# ProDoc_Schematic1_2026-05-29.net
KiCad netlist of a schematic drawn in EasyEDA Pro
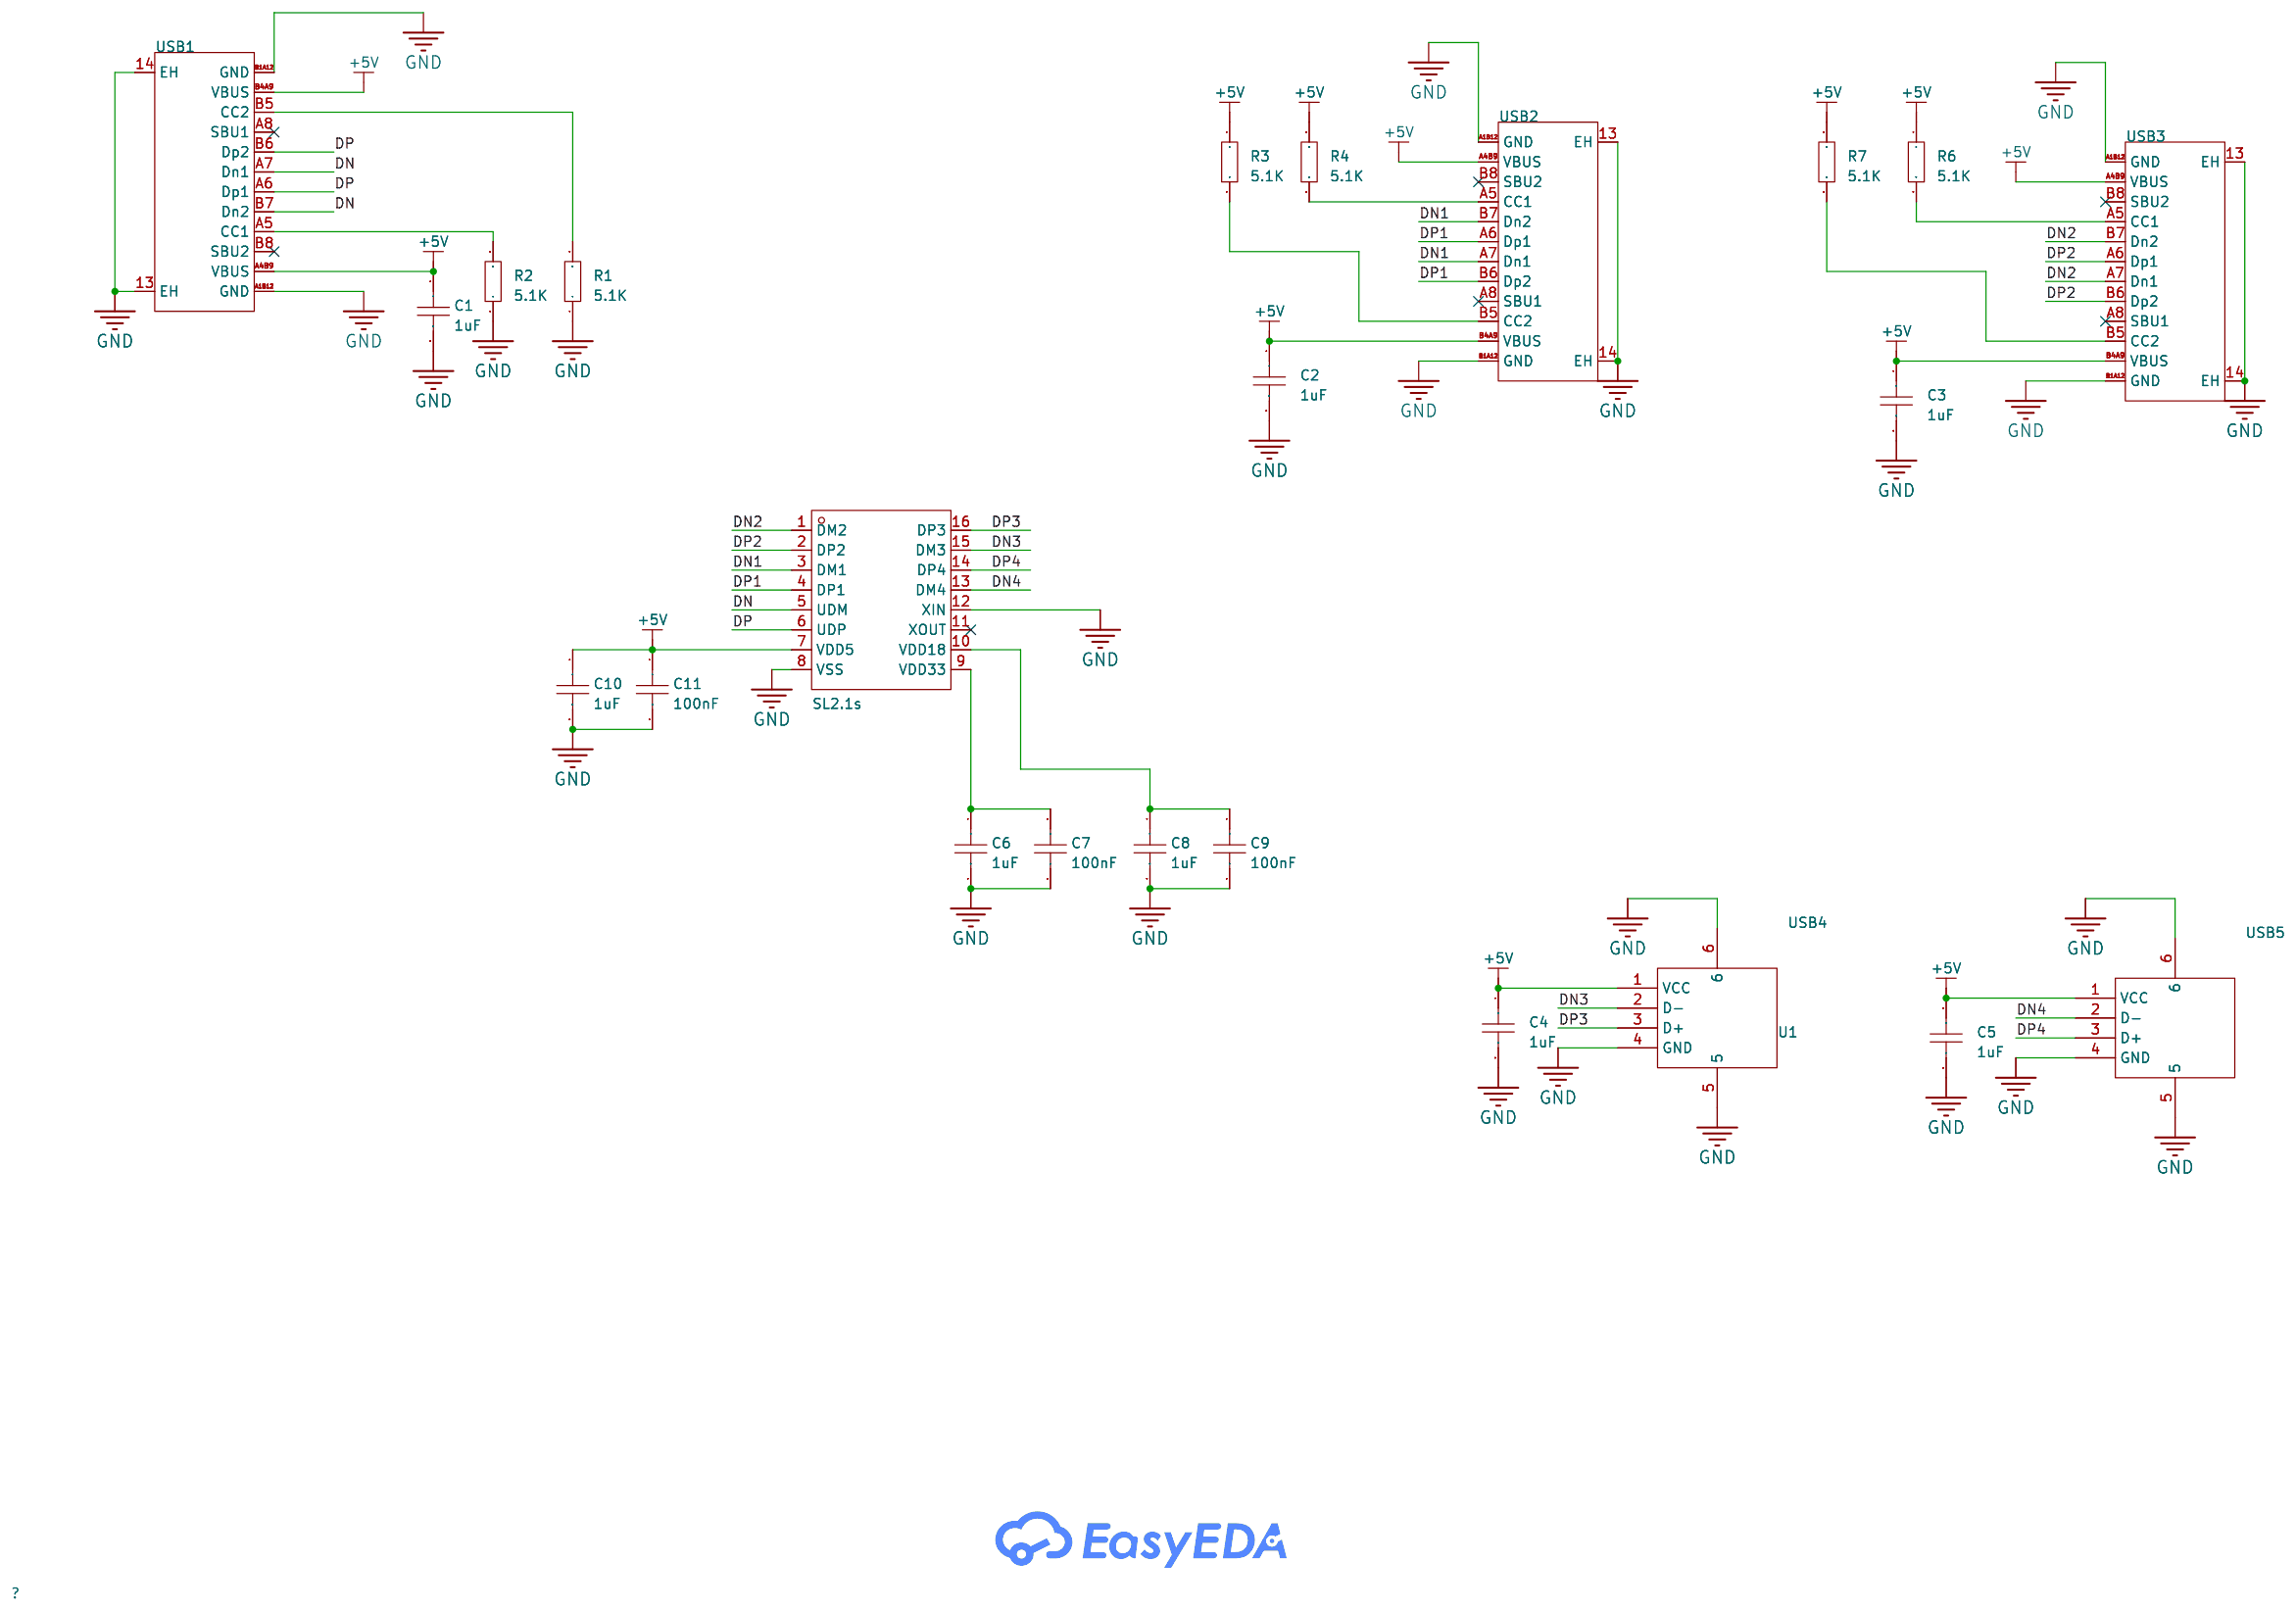
[diagram p0: schematic sheet]

(export (version "E")
  (design (tool "Eeschema 10.0.6"))
  (components
    (comp (ref "C1") (value "1uF") (footprint "easyedapro:C0603") (libsource (lib "easyedapro") (part "CAP")))
    (comp (ref "C2") (value "1uF") (footprint "easyedapro:C0603") (libsource (lib "easyedapro") (part "CAP")))
    (comp (ref "C3") (value "1uF") (footprint "easyedapro:C0603") (libsource (lib "easyedapro") (part "CAP")))
    (comp (ref "C4") (value "1uF") (footprint "easyedapro:C0603") (libsource (lib "easyedapro") (part "CAP")))
    (comp (ref "C5") (value "1uF") (footprint "easyedapro:C0603") (libsource (lib "easyedapro") (part "CAP")))
    (comp (ref "C6") (value "1uF") (footprint "easyedapro:C0603") (libsource (lib "easyedapro") (part "CAP")))
    (comp (ref "C7")
      (value "100nF")
      (footprint "easyedapro:C0603")
      (libsource (lib "easyedapro") (part "CAP"))
    )
    (comp (ref "C8") (value "1uF") (footprint "easyedapro:C0603") (libsource (lib "easyedapro") (part "CAP")))
    (comp (ref "C9")
      (value "100nF")
      (footprint "easyedapro:C0603")
      (libsource (lib "easyedapro") (part "CAP"))
    )
    (comp (ref "C10")
      (value "1uF")
      (footprint "easyedapro:C0603")
      (libsource (lib "easyedapro") (part "CAP"))
    )
    (comp (ref "C11")
      (value "100nF")
      (footprint "easyedapro:C0603")
      (libsource (lib "easyedapro") (part "CAP"))
    )
    (comp (ref "R1")
      (value "5.1K")
      (footprint "easyedapro:R0603")
      (libsource (lib "easyedapro") (part "Res"))
    )
    (comp (ref "R2")
      (value "5.1K")
      (footprint "easyedapro:R0603")
      (libsource (lib "easyedapro") (part "Res"))
    )
    (comp (ref "R3")
      (value "5.1K")
      (footprint "easyedapro:R0603")
      (libsource (lib "easyedapro") (part "Res"))
    )
    (comp (ref "R4")
      (value "5.1K")
      (footprint "easyedapro:R0603")
      (libsource (lib "easyedapro") (part "Res"))
    )
    (comp (ref "R6")
      (value "5.1K")
      (footprint "easyedapro:R0603")
      (libsource (lib "easyedapro") (part "Res"))
    )
    (comp (ref "R7")
      (value "5.1K")
      (footprint "easyedapro:R0603")
      (libsource (lib "easyedapro") (part "Res"))
    )
    (comp (ref "U1")
      (value "SL2.1s")
      (footprint "easyedapro:SSOP-16_L4.6-W2.6-P0.53-LS4.0-BL")
      (fields (field (name "Manufacturer") "CoreChips(和芯润德)"))
      (libsource (lib "easyedapro") (part "SL2.1S"))
    )
    (comp (ref "USB1")
      (value "TYPE-C 16PIN 2MD(073)")
      (footprint "easyedapro:USB-C-SMD_TYPE-C-16PIN-2MD-073")
      (fields (field (name "Manufacturer") "SHOU HAN(首韩)"))
      (libsource (lib "easyedapro") (part "TYPE-C 16PIN 2MD(073)"))
    )
    (comp (ref "USB2")
      (value "TYPE-C 16PIN 2MD(073)")
      (footprint "easyedapro:USB-C-SMD_TYPE-C-16PIN-2MD-073")
      (fields (field (name "Manufacturer") "SHOU HAN(首韩)"))
      (libsource (lib "easyedapro") (part "TYPE-C 16PIN 2MD(073)"))
    )
    (comp (ref "USB3")
      (value "TYPE-C 16PIN 2MD(073)")
      (footprint "easyedapro:USB-C-SMD_TYPE-C-16PIN-2MD-073")
      (fields (field (name "Manufacturer") "SHOU HAN(首韩)"))
      (libsource (lib "easyedapro") (part "TYPE-C 16PIN 2MD(073)"))
    )
    (comp (ref "USB4")
      (value "10.0 QHHTZB6.3")
      (footprint "easyedapro:USB-A-TH_10.0QHHTZB6.3")
      (fields (field (name "Manufacturer") "SHOU HAN(首韩)"))
      (libsource (lib "easyedapro") (part "10.0 QHHTZB6.3"))
    )
    (comp (ref "USB5")
      (value "10.0 QHHTZB6.3")
      (footprint "easyedapro:USB-A-TH_10.0QHHTZB6.3")
      (fields (field (name "Manufacturer") "SHOU HAN(首韩)"))
      (libsource (lib "easyedapro") (part "10.0 QHHTZB6.3"))
    )
  )
  (nets
    (net (code "1") (name "+5V") (class "Default")
      (node (ref "C1") (pin "1") (pinfunction "1_1") (pintype "input"))
      (node (ref "C10") (pin "1") (pinfunction "1_1") (pintype "input"))
      (node (ref "C11") (pin "1") (pinfunction "1_1") (pintype "input"))
      (node (ref "C2") (pin "1") (pinfunction "1_1") (pintype "input"))
      (node (ref "C3") (pin "1") (pinfunction "1_1") (pintype "input"))
      (node (ref "C4") (pin "1") (pinfunction "1_1") (pintype "input"))
      (node (ref "C5") (pin "1") (pinfunction "1_1") (pintype "input"))
      (node (ref "R3") (pin "1") (pinfunction "1_1") (pintype "input"))
      (node (ref "R4") (pin "1") (pinfunction "1_1") (pintype "input"))
      (node (ref "R6") (pin "1") (pinfunction "1_1") (pintype "input"))
      (node (ref "R7") (pin "1") (pinfunction "1_1") (pintype "input"))
      (node (ref "U1") (pin "7") (pinfunction "VDD5_7") (pintype "unspecified"))
      (node (ref "USB1") (pin "A4B9") (pinfunction "VBUS_A4B9") (pintype "unspecified"))
      (node (ref "USB1") (pin "B4A9") (pinfunction "VBUS_B4A9") (pintype "unspecified"))
      (node (ref "USB2") (pin "A4B9") (pinfunction "VBUS_A4B9") (pintype "unspecified"))
      (node (ref "USB2") (pin "B4A9") (pinfunction "VBUS_B4A9") (pintype "unspecified"))
      (node (ref "USB3") (pin "A4B9") (pinfunction "VBUS_A4B9") (pintype "unspecified"))
      (node (ref "USB3") (pin "B4A9") (pinfunction "VBUS_B4A9") (pintype "unspecified"))
      (node (ref "USB4") (pin "1") (pinfunction "VCC_1") (pintype "unspecified"))
      (node (ref "USB5") (pin "1") (pinfunction "VCC_1") (pintype "unspecified"))
    )
    (net (code "2") (name "/DN") (class "Default")
      (node (ref "U1") (pin "5") (pinfunction "UDM_5") (pintype "unspecified"))
      (node (ref "USB1") (pin "A7") (pinfunction "Dn1_A7") (pintype "unspecified"))
      (node (ref "USB1") (pin "B7") (pinfunction "Dn2_B7") (pintype "unspecified"))
    )
    (net (code "3") (name "/DN1") (class "Default")
      (node (ref "U1") (pin "3") (pinfunction "DM1_3") (pintype "unspecified"))
      (node (ref "USB2") (pin "A7") (pinfunction "Dn1_A7") (pintype "unspecified"))
      (node (ref "USB2") (pin "B7") (pinfunction "Dn2_B7") (pintype "unspecified"))
    )
    (net (code "4") (name "/DN2") (class "Default")
      (node (ref "U1") (pin "1") (pinfunction "DM2_1") (pintype "unspecified"))
      (node (ref "USB3") (pin "A7") (pinfunction "Dn1_A7") (pintype "unspecified"))
      (node (ref "USB3") (pin "B7") (pinfunction "Dn2_B7") (pintype "unspecified"))
    )
    (net (code "5") (name "/DN3") (class "Default")
      (node (ref "U1") (pin "15") (pinfunction "DM3_15") (pintype "unspecified"))
      (node (ref "USB4") (pin "2") (pinfunction "D-_2") (pintype "unspecified"))
    )
    (net (code "6") (name "/DN4") (class "Default")
      (node (ref "U1") (pin "13") (pinfunction "DM4_13") (pintype "unspecified"))
      (node (ref "USB5") (pin "2") (pinfunction "D-_2") (pintype "unspecified"))
    )
    (net (code "7") (name "/DP") (class "Default")
      (node (ref "U1") (pin "6") (pinfunction "UDP_6") (pintype "unspecified"))
      (node (ref "USB1") (pin "A6") (pinfunction "Dp1_A6") (pintype "unspecified"))
      (node (ref "USB1") (pin "B6") (pinfunction "Dp2_B6") (pintype "unspecified"))
    )
    (net (code "8") (name "/DP1") (class "Default")
      (node (ref "U1") (pin "4") (pinfunction "DP1_4") (pintype "unspecified"))
      (node (ref "USB2") (pin "A6") (pinfunction "Dp1_A6") (pintype "unspecified"))
      (node (ref "USB2") (pin "B6") (pinfunction "Dp2_B6") (pintype "unspecified"))
    )
    (net (code "9") (name "/DP2") (class "Default")
      (node (ref "U1") (pin "2") (pinfunction "DP2_2") (pintype "unspecified"))
      (node (ref "USB3") (pin "A6") (pinfunction "Dp1_A6") (pintype "unspecified"))
      (node (ref "USB3") (pin "B6") (pinfunction "Dp2_B6") (pintype "unspecified"))
    )
    (net (code "10") (name "/DP3") (class "Default")
      (node (ref "U1") (pin "16") (pinfunction "DP3_16") (pintype "unspecified"))
      (node (ref "USB4") (pin "3") (pinfunction "D+_3") (pintype "unspecified"))
    )
    (net (code "11") (name "/DP4") (class "Default")
      (node (ref "U1") (pin "14") (pinfunction "DP4_14") (pintype "unspecified"))
      (node (ref "USB5") (pin "3") (pinfunction "D+_3") (pintype "unspecified"))
    )
    (net (code "12") (name "GND") (class "Default")
      (node (ref "C1") (pin "2") (pinfunction "2_2") (pintype "input"))
      (node (ref "C10") (pin "2") (pinfunction "2_2") (pintype "input"))
      (node (ref "C11") (pin "2") (pinfunction "2_2") (pintype "input"))
      (node (ref "C2") (pin "2") (pinfunction "2_2") (pintype "input"))
      (node (ref "C3") (pin "2") (pinfunction "2_2") (pintype "input"))
      (node (ref "C4") (pin "2") (pinfunction "2_2") (pintype "input"))
      (node (ref "C5") (pin "2") (pinfunction "2_2") (pintype "input"))
      (node (ref "C6") (pin "2") (pinfunction "2_2") (pintype "input"))
      (node (ref "C7") (pin "2") (pinfunction "2_2") (pintype "input"))
      (node (ref "C8") (pin "2") (pinfunction "2_2") (pintype "input"))
      (node (ref "C9") (pin "2") (pinfunction "2_2") (pintype "input"))
      (node (ref "R1") (pin "1") (pinfunction "1_1") (pintype "input"))
      (node (ref "R2") (pin "1") (pinfunction "1_1") (pintype "input"))
      (node (ref "U1") (pin "12") (pinfunction "XIN_12") (pintype "unspecified"))
      (node (ref "U1") (pin "8") (pinfunction "VSS_8") (pintype "unspecified"))
      (node (ref "USB1") (pin "13") (pinfunction "EH_13") (pintype "unspecified"))
      (node (ref "USB1") (pin "14") (pinfunction "EH_14") (pintype "unspecified"))
      (node (ref "USB1") (pin "A1B12") (pinfunction "GND_A1B12") (pintype "unspecified"))
      (node (ref "USB1") (pin "B1A12") (pinfunction "GND_B1A12") (pintype "unspecified"))
      (node (ref "USB2") (pin "13") (pinfunction "EH_13") (pintype "unspecified"))
      (node (ref "USB2") (pin "14") (pinfunction "EH_14") (pintype "unspecified"))
      (node (ref "USB2") (pin "A1B12") (pinfunction "GND_A1B12") (pintype "unspecified"))
      (node (ref "USB2") (pin "B1A12") (pinfunction "GND_B1A12") (pintype "unspecified"))
      (node (ref "USB3") (pin "13") (pinfunction "EH_13") (pintype "unspecified"))
      (node (ref "USB3") (pin "14") (pinfunction "EH_14") (pintype "unspecified"))
      (node (ref "USB3") (pin "A1B12") (pinfunction "GND_A1B12") (pintype "unspecified"))
      (node (ref "USB3") (pin "B1A12") (pinfunction "GND_B1A12") (pintype "unspecified"))
      (node (ref "USB4") (pin "4") (pinfunction "GND_4") (pintype "unspecified"))
      (node (ref "USB4") (pin "5") (pinfunction "5_5") (pintype "unspecified"))
      (node (ref "USB4") (pin "6") (pinfunction "6_6") (pintype "unspecified"))
      (node (ref "USB5") (pin "4") (pinfunction "GND_4") (pintype "unspecified"))
      (node (ref "USB5") (pin "5") (pinfunction "5_5") (pintype "unspecified"))
      (node (ref "USB5") (pin "6") (pinfunction "6_6") (pintype "unspecified"))
    )
    (net (code "13") (name "Net-(U1-VDD18)") (class "Default")
      (node (ref "C8") (pin "1") (pinfunction "1_1") (pintype "input"))
      (node (ref "C9") (pin "1") (pinfunction "1_1") (pintype "input"))
      (node (ref "U1") (pin "10") (pinfunction "VDD18_10") (pintype "unspecified"))
    )
    (net (code "14") (name "Net-(U1-VDD33)") (class "Default")
      (node (ref "C6") (pin "1") (pinfunction "1_1") (pintype "input"))
      (node (ref "C7") (pin "1") (pinfunction "1_1") (pintype "input"))
      (node (ref "U1") (pin "9") (pinfunction "VDD33_9") (pintype "unspecified"))
    )
    (net (code "15") (name "Net-(USB1-CC1)") (class "Default")
      (node (ref "R2") (pin "2") (pinfunction "2_2") (pintype "input"))
      (node (ref "USB1") (pin "A5") (pinfunction "CC1_A5") (pintype "unspecified"))
    )
    (net (code "16") (name "Net-(USB1-CC2)") (class "Default")
      (node (ref "R1") (pin "2") (pinfunction "2_2") (pintype "input"))
      (node (ref "USB1") (pin "B5") (pinfunction "CC2_B5") (pintype "unspecified"))
    )
    (net (code "17") (name "Net-(USB2-CC1)") (class "Default")
      (node (ref "R4") (pin "2") (pinfunction "2_2") (pintype "input"))
      (node (ref "USB2") (pin "A5") (pinfunction "CC1_A5") (pintype "unspecified"))
    )
    (net (code "18") (name "Net-(USB2-CC2)") (class "Default")
      (node (ref "R3") (pin "2") (pinfunction "2_2") (pintype "input"))
      (node (ref "USB2") (pin "B5") (pinfunction "CC2_B5") (pintype "unspecified"))
    )
    (net (code "19") (name "Net-(USB3-CC1)") (class "Default")
      (node (ref "R6") (pin "2") (pinfunction "2_2") (pintype "input"))
      (node (ref "USB3") (pin "A5") (pinfunction "CC1_A5") (pintype "unspecified"))
    )
    (net (code "20") (name "Net-(USB3-CC2)") (class "Default")
      (node (ref "R7") (pin "2") (pinfunction "2_2") (pintype "input"))
      (node (ref "USB3") (pin "B5") (pinfunction "CC2_B5") (pintype "unspecified"))
    )
    (net (code "21") (name "unconnected-(U1-XOUT-Pad11)") (class "Default")
      (node (ref "U1") (pin "11") (pinfunction "XOUT_11") (pintype "unspecified+no_connect"))
    )
    (net (code "22") (name "unconnected-(USB1-SBU1-PadA8)") (class "Default")
      (node (ref "USB1") (pin "A8") (pinfunction "SBU1_A8") (pintype "unspecified+no_connect"))
    )
    (net (code "23") (name "unconnected-(USB1-SBU2-PadB8)") (class "Default")
      (node (ref "USB1") (pin "B8") (pinfunction "SBU2_B8") (pintype "unspecified+no_connect"))
    )
    (net (code "24") (name "unconnected-(USB2-SBU1-PadA8)") (class "Default")
      (node (ref "USB2") (pin "A8") (pinfunction "SBU1_A8") (pintype "unspecified+no_connect"))
    )
    (net (code "25") (name "unconnected-(USB2-SBU2-PadB8)") (class "Default")
      (node (ref "USB2") (pin "B8") (pinfunction "SBU2_B8") (pintype "unspecified+no_connect"))
    )
    (net (code "26") (name "unconnected-(USB3-SBU1-PadA8)") (class "Default")
      (node (ref "USB3") (pin "A8") (pinfunction "SBU1_A8") (pintype "unspecified+no_connect"))
    )
    (net (code "27") (name "unconnected-(USB3-SBU2-PadB8)") (class "Default")
      (node (ref "USB3") (pin "B8") (pinfunction "SBU2_B8") (pintype "unspecified+no_connect"))
    )
  )
)
